# Interconnect_board_v1p3.net
KiCad netlist of a schematic drawn in EAGLE
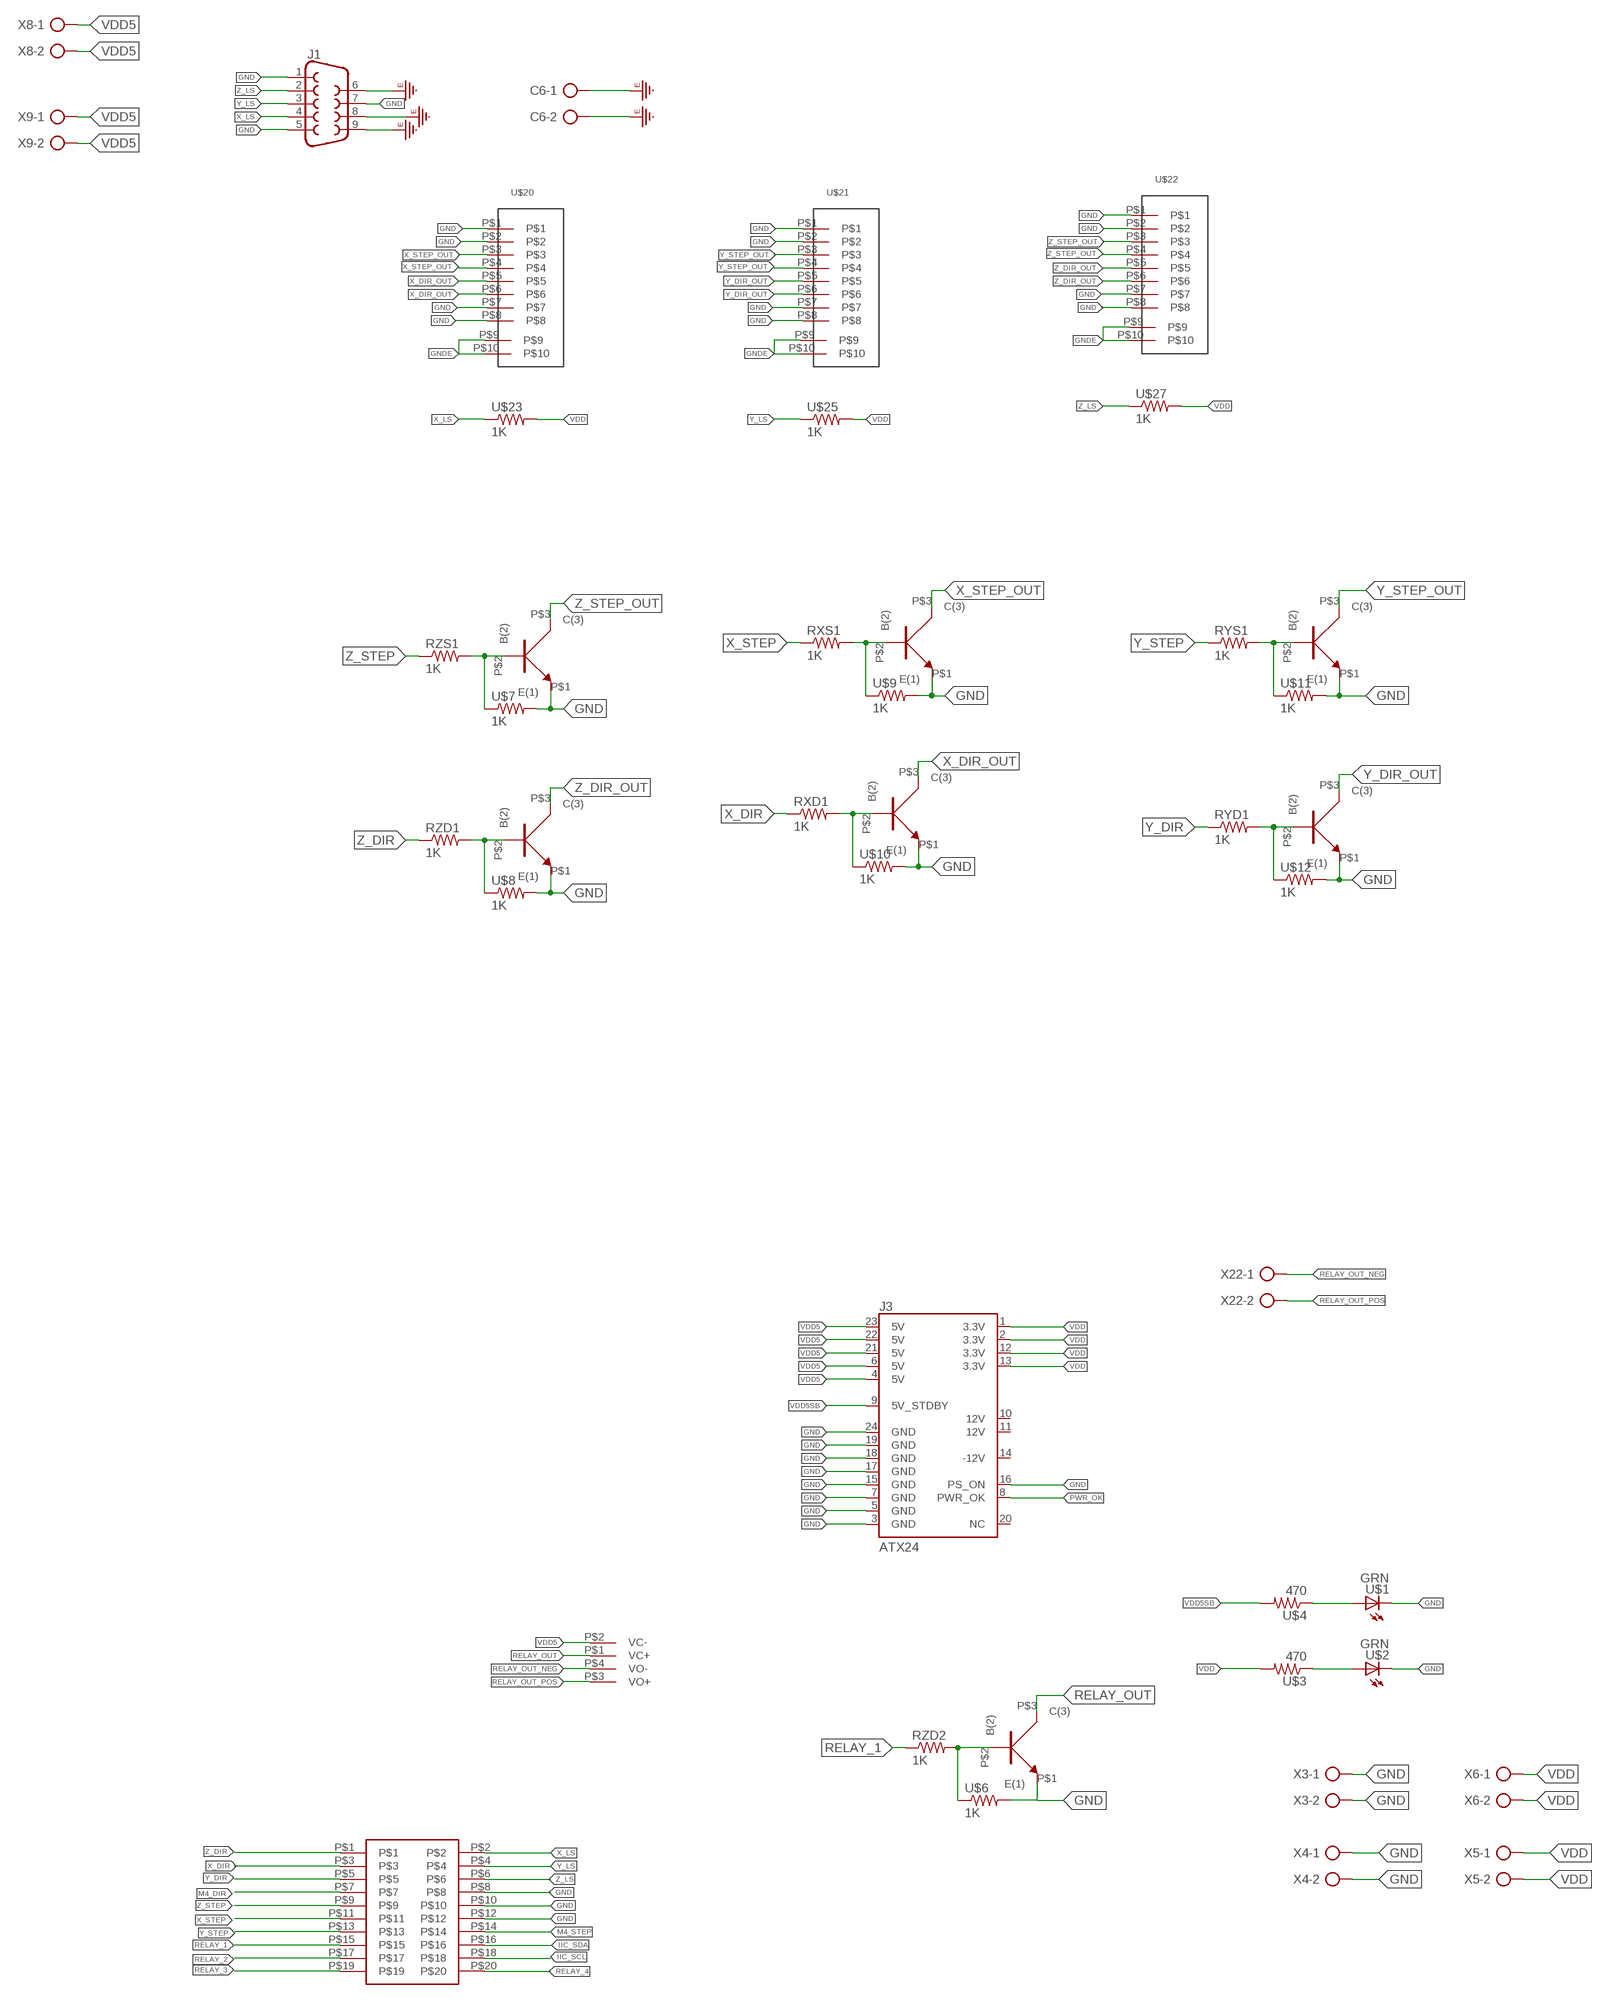
[diagram p0: schematic, sheet 1]

(export (version "E")
  (design (tool "Eeschema 10.0.6"))
  (components
    (comp (ref "C6")
      (value "AK300/2")
      (footprint "eagle-import:AK300_2")
      (libsource (lib "eagle-import") (part "AK300/2"))
    )
    (comp (ref "J1")
      (value "DB9MALE")
      (footprint "eagle-import:DB9_MALE")
      (libsource (lib "eagle-import") (part "DB9MALE"))
    )
    (comp (ref "J3")
      (value "ATX24")
      (footprint "eagle-import:ATX24_STRAIGHT")
      (libsource (lib "eagle-import") (part "ATX24"))
    )
    (comp (ref "RXD1")
      (value "R_0805_1K")
      (footprint "eagle-import:R_0805_1K")
      (libsource (lib "eagle-import") (part "R_0805_1K"))
    )
    (comp (ref "RXS1")
      (value "R_0805_1K")
      (footprint "eagle-import:R_0805_1K")
      (libsource (lib "eagle-import") (part "R_0805_1K"))
    )
    (comp (ref "RYD1")
      (value "R_0805_1K")
      (footprint "eagle-import:R_0805_1K")
      (libsource (lib "eagle-import") (part "R_0805_1K"))
    )
    (comp (ref "RYS1")
      (value "R_0805_1K")
      (footprint "eagle-import:R_0805_1K")
      (libsource (lib "eagle-import") (part "R_0805_1K"))
    )
    (comp (ref "RZD1")
      (value "R_0805_1K")
      (footprint "eagle-import:R_0805_1K")
      (libsource (lib "eagle-import") (part "R_0805_1K"))
    )
    (comp (ref "RZD2")
      (value "R_0805_1K")
      (footprint "eagle-import:R_0805_1K")
      (libsource (lib "eagle-import") (part "R_0805_1K"))
    )
    (comp (ref "RZS1")
      (value "R_0805_1K")
      (footprint "eagle-import:R_0805_1K")
      (libsource (lib "eagle-import") (part "R_0805_1K"))
    )
    (comp (ref "U$1")
      (value "LED_0805_GREEN")
      (footprint "eagle-import:LED_0805_GREEN")
      (libsource (lib "eagle-import") (part "LED_0805_GREEN"))
    )
    (comp (ref "U$2")
      (value "LED_0805_GREEN")
      (footprint "eagle-import:LED_0805_GREEN")
      (libsource (lib "eagle-import") (part "LED_0805_GREEN"))
    )
    (comp (ref "U$3")
      (value "R_0805_470")
      (footprint "eagle-import:R_0805_470")
      (libsource (lib "eagle-import") (part "R_0805_470"))
    )
    (comp (ref "U$4")
      (value "R_0805_470")
      (footprint "eagle-import:R_0805_470")
      (libsource (lib "eagle-import") (part "R_0805_470"))
    )
    (comp (ref "U$5")
      (value "RELAY_KYOTO_KF0604D")
      (footprint "eagle-import:RELAY_KYOTO_KF0604D")
      (libsource (lib "eagle-import") (part "RELAY_KYOTO_KF0604D"))
    )
    (comp (ref "U$6")
      (value "R_0805_1K")
      (footprint "eagle-import:R_0805_1K")
      (libsource (lib "eagle-import") (part "R_0805_1K"))
    )
    (comp (ref "U$7")
      (value "R_0805_1K")
      (footprint "eagle-import:R_0805_1K")
      (libsource (lib "eagle-import") (part "R_0805_1K"))
    )
    (comp (ref "U$8")
      (value "R_0805_1K")
      (footprint "eagle-import:R_0805_1K")
      (libsource (lib "eagle-import") (part "R_0805_1K"))
    )
    (comp (ref "U$9")
      (value "R_0805_1K")
      (footprint "eagle-import:R_0805_1K")
      (libsource (lib "eagle-import") (part "R_0805_1K"))
    )
    (comp (ref "U$10")
      (value "R_0805_1K")
      (footprint "eagle-import:R_0805_1K")
      (libsource (lib "eagle-import") (part "R_0805_1K"))
    )
    (comp (ref "U$11")
      (value "R_0805_1K")
      (footprint "eagle-import:R_0805_1K")
      (libsource (lib "eagle-import") (part "R_0805_1K"))
    )
    (comp (ref "U$12")
      (value "R_0805_1K")
      (footprint "eagle-import:R_0805_1K")
      (libsource (lib "eagle-import") (part "R_0805_1K"))
    )
    (comp (ref "U$13")
      (value "TRANS_NPN")
      (footprint "eagle-import:TO_92_STRAIGHT")
      (libsource (lib "eagle-import") (part "TRANS_NPN"))
    )
    (comp (ref "U$14")
      (value "TRANS_NPN")
      (footprint "eagle-import:TO_92_STRAIGHT")
      (libsource (lib "eagle-import") (part "TRANS_NPN"))
    )
    (comp (ref "U$15")
      (value "TRANS_NPN")
      (footprint "eagle-import:TO_92_STRAIGHT")
      (libsource (lib "eagle-import") (part "TRANS_NPN"))
    )
    (comp (ref "U$16")
      (value "TRANS_NPN")
      (footprint "eagle-import:TO_92_STRAIGHT")
      (libsource (lib "eagle-import") (part "TRANS_NPN"))
    )
    (comp (ref "U$17")
      (value "TRANS_NPN")
      (footprint "eagle-import:TO_92_STRAIGHT")
      (libsource (lib "eagle-import") (part "TRANS_NPN"))
    )
    (comp (ref "U$18")
      (value "TRANS_NPN")
      (footprint "eagle-import:TO_92_STRAIGHT")
      (libsource (lib "eagle-import") (part "TRANS_NPN"))
    )
    (comp (ref "U$19")
      (value "TRANS_NPN")
      (footprint "eagle-import:TO_92_STRAIGHT")
      (libsource (lib "eagle-import") (part "TRANS_NPN"))
    )
    (comp (ref "U$20")
      (value "RJ45_SMTRJ")
      (footprint "eagle-import:RJ45_SMT")
      (libsource (lib "eagle-import") (part "RJ45_SMTRJ"))
    )
    (comp (ref "U$21")
      (value "RJ45_SMTRJ")
      (footprint "eagle-import:RJ45_SMT")
      (libsource (lib "eagle-import") (part "RJ45_SMTRJ"))
    )
    (comp (ref "U$22")
      (value "RJ45_SMTRJ")
      (footprint "eagle-import:RJ45_SMT")
      (libsource (lib "eagle-import") (part "RJ45_SMTRJ"))
    )
    (comp (ref "U$23")
      (value "R_0805_1K")
      (footprint "eagle-import:R_0805_1K")
      (libsource (lib "eagle-import") (part "R_0805_1K"))
    )
    (comp (ref "U$25")
      (value "R_0805_1K")
      (footprint "eagle-import:R_0805_1K")
      (libsource (lib "eagle-import") (part "R_0805_1K"))
    )
    (comp (ref "U$26")
      (value "2_X_10_HEADER_GENERIC")
      (footprint "eagle-import:2_X_10_.1_INCH")
      (libsource (lib "eagle-import") (part "2_X_10_HEADER_GENERIC"))
    )
    (comp (ref "U$27")
      (value "R_0805_1K")
      (footprint "eagle-import:R_0805_1K")
      (libsource (lib "eagle-import") (part "R_0805_1K"))
    )
    (comp (ref "X3")
      (value "AK300/2")
      (footprint "eagle-import:AK300_2")
      (libsource (lib "eagle-import") (part "AK300/2"))
    )
    (comp (ref "X4")
      (value "AK300/2")
      (footprint "eagle-import:AK300_2")
      (libsource (lib "eagle-import") (part "AK300/2"))
    )
    (comp (ref "X5")
      (value "AK300/2")
      (footprint "eagle-import:AK300_2")
      (libsource (lib "eagle-import") (part "AK300/2"))
    )
    (comp (ref "X6")
      (value "AK300/2")
      (footprint "eagle-import:AK300_2")
      (libsource (lib "eagle-import") (part "AK300/2"))
    )
    (comp (ref "X8")
      (value "AK300/2")
      (footprint "eagle-import:AK300_2")
      (libsource (lib "eagle-import") (part "AK300/2"))
    )
    (comp (ref "X9")
      (value "AK300/2")
      (footprint "eagle-import:AK300_2")
      (libsource (lib "eagle-import") (part "AK300/2"))
    )
    (comp (ref "X22")
      (value "AK300/2")
      (footprint "eagle-import:AK300_2")
      (libsource (lib "eagle-import") (part "AK300/2"))
    )
  )
  (nets
    (net (code "1") (name "GND") (class "Default")
      (node (ref "J1") (pin "1") (pinfunction "1_1") (pintype "passive"))
      (node (ref "J1") (pin "5") (pinfunction "5_5") (pintype "passive"))
      (node (ref "J1") (pin "7") (pinfunction "7_7") (pintype "passive"))
      (node (ref "J3") (pin "15") (pinfunction "GND_15") (pintype "bidirectional"))
      (node (ref "J3") (pin "16") (pinfunction "PS_ON_16") (pintype "bidirectional"))
      (node (ref "J3") (pin "17") (pinfunction "GND_17") (pintype "bidirectional"))
      (node (ref "J3") (pin "18") (pinfunction "GND_18") (pintype "bidirectional"))
      (node (ref "J3") (pin "19") (pinfunction "GND_19") (pintype "bidirectional"))
      (node (ref "J3") (pin "24") (pinfunction "GND_24") (pintype "bidirectional"))
      (node (ref "J3") (pin "3") (pinfunction "GND_3") (pintype "bidirectional"))
      (node (ref "J3") (pin "5") (pinfunction "GND_5") (pintype "bidirectional"))
      (node (ref "J3") (pin "7") (pinfunction "GND_7") (pintype "bidirectional"))
      (node (ref "U$1") (pin "C") (pinfunction "C_C") (pintype "passive"))
      (node (ref "U$10") (pin "2") (pinfunction "2_2") (pintype "passive"))
      (node (ref "U$11") (pin "2") (pinfunction "2_2") (pintype "passive"))
      (node (ref "U$12") (pin "2") (pinfunction "2_2") (pintype "passive"))
      (node (ref "U$13") (pin "P$1") (pinfunction "E(1)_P$1") (pintype "output"))
      (node (ref "U$14") (pin "P$1") (pinfunction "E(1)_P$1") (pintype "output"))
      (node (ref "U$15") (pin "P$1") (pinfunction "E(1)_P$1") (pintype "output"))
      (node (ref "U$16") (pin "P$1") (pinfunction "E(1)_P$1") (pintype "output"))
      (node (ref "U$17") (pin "P$1") (pinfunction "E(1)_P$1") (pintype "output"))
      (node (ref "U$18") (pin "P$1") (pinfunction "E(1)_P$1") (pintype "output"))
      (node (ref "U$19") (pin "P$1") (pinfunction "E(1)_P$1") (pintype "output"))
      (node (ref "U$2") (pin "C") (pinfunction "C_C") (pintype "passive"))
      (node (ref "U$20") (pin "P$1") (pinfunction "P$1_P$1") (pintype "bidirectional"))
      (node (ref "U$20") (pin "P$2") (pinfunction "P$2_P$2") (pintype "bidirectional"))
      (node (ref "U$20") (pin "P$7") (pinfunction "P$7_P$7") (pintype "bidirectional"))
      (node (ref "U$20") (pin "P$8") (pinfunction "P$8_P$8") (pintype "bidirectional"))
      (node (ref "U$21") (pin "P$1") (pinfunction "P$1_P$1") (pintype "bidirectional"))
      (node (ref "U$21") (pin "P$2") (pinfunction "P$2_P$2") (pintype "bidirectional"))
      (node (ref "U$21") (pin "P$7") (pinfunction "P$7_P$7") (pintype "bidirectional"))
      (node (ref "U$21") (pin "P$8") (pinfunction "P$8_P$8") (pintype "bidirectional"))
      (node (ref "U$22") (pin "P$1") (pinfunction "P$1_P$1") (pintype "bidirectional"))
      (node (ref "U$22") (pin "P$2") (pinfunction "P$2_P$2") (pintype "bidirectional"))
      (node (ref "U$22") (pin "P$7") (pinfunction "P$7_P$7") (pintype "bidirectional"))
      (node (ref "U$22") (pin "P$8") (pinfunction "P$8_P$8") (pintype "bidirectional"))
      (node (ref "U$26") (pin "P$10") (pinfunction "P$10_P$10") (pintype "bidirectional"))
      (node (ref "U$26") (pin "P$12") (pinfunction "P$12_P$12") (pintype "bidirectional"))
      (node (ref "U$26") (pin "P$8") (pinfunction "P$8_P$8") (pintype "bidirectional"))
      (node (ref "U$6") (pin "2") (pinfunction "2_2") (pintype "passive"))
      (node (ref "U$7") (pin "2") (pinfunction "2_2") (pintype "passive"))
      (node (ref "U$8") (pin "2") (pinfunction "2_2") (pintype "passive"))
      (node (ref "U$9") (pin "2") (pinfunction "2_2") (pintype "passive"))
      (node (ref "X3") (pin "1") (pinfunction "KL_1") (pintype "passive"))
      (node (ref "X3") (pin "2") (pinfunction "KL_2") (pintype "passive"))
      (node (ref "X4") (pin "1") (pinfunction "KL_1") (pintype "passive"))
      (node (ref "X4") (pin "2") (pinfunction "KL_2") (pintype "passive"))
    )
    (net (code "2") (name "GNDE") (class "Default")
      (node (ref "C6") (pin "1") (pinfunction "KL_1") (pintype "passive"))
      (node (ref "C6") (pin "2") (pinfunction "KL_2") (pintype "passive"))
      (node (ref "J1") (pin "6") (pinfunction "6_6") (pintype "passive"))
      (node (ref "J1") (pin "8") (pinfunction "8_8") (pintype "passive"))
      (node (ref "J1") (pin "9") (pinfunction "9_9") (pintype "passive"))
      (node (ref "U$20") (pin "P$10") (pinfunction "P$10_P$10") (pintype "bidirectional"))
      (node (ref "U$20") (pin "P$9") (pinfunction "P$9_P$9") (pintype "bidirectional"))
      (node (ref "U$21") (pin "P$10") (pinfunction "P$10_P$10") (pintype "bidirectional"))
      (node (ref "U$21") (pin "P$9") (pinfunction "P$9_P$9") (pintype "bidirectional"))
      (node (ref "U$22") (pin "P$10") (pinfunction "P$10_P$10") (pintype "bidirectional"))
      (node (ref "U$22") (pin "P$9") (pinfunction "P$9_P$9") (pintype "bidirectional"))
    )
    (net (code "3") (name "IIC_SCL") (class "Default")
      (node (ref "U$26") (pin "P$18") (pinfunction "P$18_P$18") (pintype "bidirectional"))
    )
    (net (code "4") (name "IIC_SDA") (class "Default")
      (node (ref "U$26") (pin "P$16") (pinfunction "P$16_P$16") (pintype "bidirectional"))
    )
    (net (code "5") (name "M4_DIR") (class "Default")
      (node (ref "U$26") (pin "P$7") (pinfunction "P$7_P$7") (pintype "bidirectional"))
    )
    (net (code "6") (name "M4_STEP") (class "Default")
      (node (ref "U$26") (pin "P$14") (pinfunction "P$14_P$14") (pintype "bidirectional"))
    )
    (net (code "7") (name "Net-(U$1-PadA)") (class "Default")
      (node (ref "U$1") (pin "A") (pinfunction "A_A") (pintype "passive"))
      (node (ref "U$4") (pin "1") (pinfunction "1_1") (pintype "passive"))
    )
    (net (code "8") (name "Net-(U$2-PadA)") (class "Default")
      (node (ref "U$2") (pin "A") (pinfunction "A_A") (pintype "passive"))
      (node (ref "U$3") (pin "1") (pinfunction "1_1") (pintype "passive"))
    )
    (net (code "9") (name "Net-(U$13-B(2))") (class "Default")
      (node (ref "RZS1") (pin "2") (pinfunction "2_2") (pintype "passive"))
      (node (ref "U$13") (pin "P$2") (pinfunction "B(2)_P$2") (pintype "input"))
      (node (ref "U$7") (pin "1") (pinfunction "1_1") (pintype "passive"))
    )
    (net (code "10") (name "Net-(U$14-B(2))") (class "Default")
      (node (ref "RZD1") (pin "2") (pinfunction "2_2") (pintype "passive"))
      (node (ref "U$14") (pin "P$2") (pinfunction "B(2)_P$2") (pintype "input"))
      (node (ref "U$8") (pin "1") (pinfunction "1_1") (pintype "passive"))
    )
    (net (code "11") (name "Net-(U$15-B(2))") (class "Default")
      (node (ref "RXS1") (pin "2") (pinfunction "2_2") (pintype "passive"))
      (node (ref "U$15") (pin "P$2") (pinfunction "B(2)_P$2") (pintype "input"))
      (node (ref "U$9") (pin "1") (pinfunction "1_1") (pintype "passive"))
    )
    (net (code "12") (name "Net-(U$16-B(2))") (class "Default")
      (node (ref "RXD1") (pin "2") (pinfunction "2_2") (pintype "passive"))
      (node (ref "U$10") (pin "1") (pinfunction "1_1") (pintype "passive"))
      (node (ref "U$16") (pin "P$2") (pinfunction "B(2)_P$2") (pintype "input"))
    )
    (net (code "13") (name "Net-(U$17-B(2))") (class "Default")
      (node (ref "RYD1") (pin "2") (pinfunction "2_2") (pintype "passive"))
      (node (ref "U$12") (pin "1") (pinfunction "1_1") (pintype "passive"))
      (node (ref "U$17") (pin "P$2") (pinfunction "B(2)_P$2") (pintype "input"))
    )
    (net (code "14") (name "Net-(U$18-B(2))") (class "Default")
      (node (ref "RYS1") (pin "2") (pinfunction "2_2") (pintype "passive"))
      (node (ref "U$11") (pin "1") (pinfunction "1_1") (pintype "passive"))
      (node (ref "U$18") (pin "P$2") (pinfunction "B(2)_P$2") (pintype "input"))
    )
    (net (code "15") (name "Net-(U$19-B(2))") (class "Default")
      (node (ref "RZD2") (pin "2") (pinfunction "2_2") (pintype "passive"))
      (node (ref "U$19") (pin "P$2") (pinfunction "B(2)_P$2") (pintype "input"))
      (node (ref "U$6") (pin "1") (pinfunction "1_1") (pintype "passive"))
    )
    (net (code "16") (name "PWR_OK") (class "Default")
      (node (ref "J3") (pin "8") (pinfunction "PWR_OK_8") (pintype "bidirectional"))
    )
    (net (code "17") (name "RELAY_1") (class "Default")
      (node (ref "RZD2") (pin "1") (pinfunction "1_1") (pintype "passive"))
      (node (ref "U$26") (pin "P$15") (pinfunction "P$15_P$15") (pintype "bidirectional"))
    )
    (net (code "18") (name "RELAY_2") (class "Default")
      (node (ref "U$26") (pin "P$17") (pinfunction "P$17_P$17") (pintype "bidirectional"))
    )
    (net (code "19") (name "RELAY_3") (class "Default")
      (node (ref "U$26") (pin "P$19") (pinfunction "P$19_P$19") (pintype "bidirectional"))
    )
    (net (code "20") (name "RELAY_4") (class "Default")
      (node (ref "U$26") (pin "P$20") (pinfunction "P$20_P$20") (pintype "bidirectional"))
    )
    (net (code "21") (name "RELAY_OUT") (class "Default")
      (node (ref "U$19") (pin "P$3") (pinfunction "C(3)_P$3") (pintype "input"))
      (node (ref "U$5") (pin "P$1") (pinfunction "VC+_P$1") (pintype "bidirectional"))
    )
    (net (code "22") (name "RELAY_OUT_NEG") (class "Default")
      (node (ref "U$5") (pin "P$4") (pinfunction "VO-_P$4") (pintype "bidirectional"))
      (node (ref "X22") (pin "1") (pinfunction "KL_1") (pintype "passive"))
    )
    (net (code "23") (name "RELAY_OUT_POS") (class "Default")
      (node (ref "U$5") (pin "P$3") (pinfunction "VO+_P$3") (pintype "bidirectional"))
      (node (ref "X22") (pin "2") (pinfunction "KL_2") (pintype "passive"))
    )
    (net (code "24") (name "VDD") (class "Default")
      (node (ref "J3") (pin "1") (pinfunction "3.3V_1") (pintype "bidirectional"))
      (node (ref "J3") (pin "12") (pinfunction "3.3V_12") (pintype "bidirectional"))
      (node (ref "J3") (pin "13") (pinfunction "3.3V_13") (pintype "bidirectional"))
      (node (ref "J3") (pin "2") (pinfunction "3.3V_2") (pintype "bidirectional"))
      (node (ref "U$23") (pin "2") (pinfunction "2_2") (pintype "passive"))
      (node (ref "U$25") (pin "2") (pinfunction "2_2") (pintype "passive"))
      (node (ref "U$27") (pin "2") (pinfunction "2_2") (pintype "passive"))
      (node (ref "U$3") (pin "2") (pinfunction "2_2") (pintype "passive"))
      (node (ref "X5") (pin "1") (pinfunction "KL_1") (pintype "passive"))
      (node (ref "X5") (pin "2") (pinfunction "KL_2") (pintype "passive"))
      (node (ref "X6") (pin "1") (pinfunction "KL_1") (pintype "passive"))
      (node (ref "X6") (pin "2") (pinfunction "KL_2") (pintype "passive"))
    )
    (net (code "25") (name "VDD5") (class "Default")
      (node (ref "J3") (pin "21") (pinfunction "5V_21") (pintype "bidirectional"))
      (node (ref "J3") (pin "22") (pinfunction "5V_22") (pintype "bidirectional"))
      (node (ref "J3") (pin "23") (pinfunction "5V_23") (pintype "bidirectional"))
      (node (ref "J3") (pin "4") (pinfunction "5V_4") (pintype "bidirectional"))
      (node (ref "J3") (pin "6") (pinfunction "5V_6") (pintype "bidirectional"))
      (node (ref "U$5") (pin "P$2") (pinfunction "VC-_P$2") (pintype "bidirectional"))
      (node (ref "X8") (pin "1") (pinfunction "KL_1") (pintype "passive"))
      (node (ref "X8") (pin "2") (pinfunction "KL_2") (pintype "passive"))
      (node (ref "X9") (pin "1") (pinfunction "KL_1") (pintype "passive"))
      (node (ref "X9") (pin "2") (pinfunction "KL_2") (pintype "passive"))
    )
    (net (code "26") (name "VDD5SB") (class "Default")
      (node (ref "J3") (pin "9") (pinfunction "5V_STDBY_9") (pintype "bidirectional"))
      (node (ref "U$4") (pin "2") (pinfunction "2_2") (pintype "passive"))
    )
    (net (code "27") (name "X_DIR") (class "Default")
      (node (ref "RXD1") (pin "1") (pinfunction "1_1") (pintype "passive"))
      (node (ref "U$26") (pin "P$3") (pinfunction "P$3_P$3") (pintype "bidirectional"))
    )
    (net (code "28") (name "X_DIR_OUT") (class "Default")
      (node (ref "U$16") (pin "P$3") (pinfunction "C(3)_P$3") (pintype "input"))
      (node (ref "U$20") (pin "P$5") (pinfunction "P$5_P$5") (pintype "bidirectional"))
      (node (ref "U$20") (pin "P$6") (pinfunction "P$6_P$6") (pintype "bidirectional"))
    )
    (net (code "29") (name "X_LS") (class "Default")
      (node (ref "J1") (pin "4") (pinfunction "4_4") (pintype "passive"))
      (node (ref "U$23") (pin "1") (pinfunction "1_1") (pintype "passive"))
      (node (ref "U$26") (pin "P$2") (pinfunction "P$2_P$2") (pintype "bidirectional"))
    )
    (net (code "30") (name "X_STEP") (class "Default")
      (node (ref "RXS1") (pin "1") (pinfunction "1_1") (pintype "passive"))
      (node (ref "U$26") (pin "P$11") (pinfunction "P$11_P$11") (pintype "bidirectional"))
    )
    (net (code "31") (name "X_STEP_OUT") (class "Default")
      (node (ref "U$15") (pin "P$3") (pinfunction "C(3)_P$3") (pintype "input"))
      (node (ref "U$20") (pin "P$3") (pinfunction "P$3_P$3") (pintype "bidirectional"))
      (node (ref "U$20") (pin "P$4") (pinfunction "P$4_P$4") (pintype "bidirectional"))
    )
    (net (code "32") (name "Y_DIR") (class "Default")
      (node (ref "RYD1") (pin "1") (pinfunction "1_1") (pintype "passive"))
      (node (ref "U$26") (pin "P$5") (pinfunction "P$5_P$5") (pintype "bidirectional"))
    )
    (net (code "33") (name "Y_DIR_OUT") (class "Default")
      (node (ref "U$17") (pin "P$3") (pinfunction "C(3)_P$3") (pintype "input"))
      (node (ref "U$21") (pin "P$5") (pinfunction "P$5_P$5") (pintype "bidirectional"))
      (node (ref "U$21") (pin "P$6") (pinfunction "P$6_P$6") (pintype "bidirectional"))
    )
    (net (code "34") (name "Y_LS") (class "Default")
      (node (ref "J1") (pin "3") (pinfunction "3_3") (pintype "passive"))
      (node (ref "U$25") (pin "1") (pinfunction "1_1") (pintype "passive"))
      (node (ref "U$26") (pin "P$4") (pinfunction "P$4_P$4") (pintype "bidirectional"))
    )
    (net (code "35") (name "Y_STEP") (class "Default")
      (node (ref "RYS1") (pin "1") (pinfunction "1_1") (pintype "passive"))
      (node (ref "U$26") (pin "P$13") (pinfunction "P$13_P$13") (pintype "bidirectional"))
    )
    (net (code "36") (name "Y_STEP_OUT") (class "Default")
      (node (ref "U$18") (pin "P$3") (pinfunction "C(3)_P$3") (pintype "input"))
      (node (ref "U$21") (pin "P$3") (pinfunction "P$3_P$3") (pintype "bidirectional"))
      (node (ref "U$21") (pin "P$4") (pinfunction "P$4_P$4") (pintype "bidirectional"))
    )
    (net (code "37") (name "Z_DIR") (class "Default")
      (node (ref "RZD1") (pin "1") (pinfunction "1_1") (pintype "passive"))
      (node (ref "U$26") (pin "P$1") (pinfunction "P$1_P$1") (pintype "bidirectional"))
    )
    (net (code "38") (name "Z_DIR_OUT") (class "Default")
      (node (ref "U$14") (pin "P$3") (pinfunction "C(3)_P$3") (pintype "input"))
      (node (ref "U$22") (pin "P$5") (pinfunction "P$5_P$5") (pintype "bidirectional"))
      (node (ref "U$22") (pin "P$6") (pinfunction "P$6_P$6") (pintype "bidirectional"))
    )
    (net (code "39") (name "Z_LS") (class "Default")
      (node (ref "J1") (pin "2") (pinfunction "2_2") (pintype "passive"))
      (node (ref "U$26") (pin "P$6") (pinfunction "P$6_P$6") (pintype "bidirectional"))
      (node (ref "U$27") (pin "1") (pinfunction "1_1") (pintype "passive"))
    )
    (net (code "40") (name "Z_STEP") (class "Default")
      (node (ref "RZS1") (pin "1") (pinfunction "1_1") (pintype "passive"))
      (node (ref "U$26") (pin "P$9") (pinfunction "P$9_P$9") (pintype "bidirectional"))
    )
    (net (code "41") (name "Z_STEP_OUT") (class "Default")
      (node (ref "U$13") (pin "P$3") (pinfunction "C(3)_P$3") (pintype "input"))
      (node (ref "U$22") (pin "P$3") (pinfunction "P$3_P$3") (pintype "bidirectional"))
      (node (ref "U$22") (pin "P$4") (pinfunction "P$4_P$4") (pintype "bidirectional"))
    )
    (net (code "42") (name "unconnected-(J3--12V-Pad14)") (class "Default")
      (node (ref "J3") (pin "14") (pinfunction "-12V_14") (pintype "bidirectional"))
    )
    (net (code "43") (name "unconnected-(J3-12V-Pad10)") (class "Default")
      (node (ref "J3") (pin "10") (pinfunction "12V_10") (pintype "bidirectional"))
    )
    (net (code "44") (name "unconnected-(J3-12V-Pad11)") (class "Default")
      (node (ref "J3") (pin "11") (pinfunction "12V_11") (pintype "bidirectional"))
    )
    (net (code "45") (name "unconnected-(J3-NC-Pad20)") (class "Default")
      (node (ref "J3") (pin "20") (pinfunction "NC_20") (pintype "bidirectional"))
    )
  )
)
